# LED_CUBE_V4.net
KiCad netlist of a schematic drawn in EAGLE
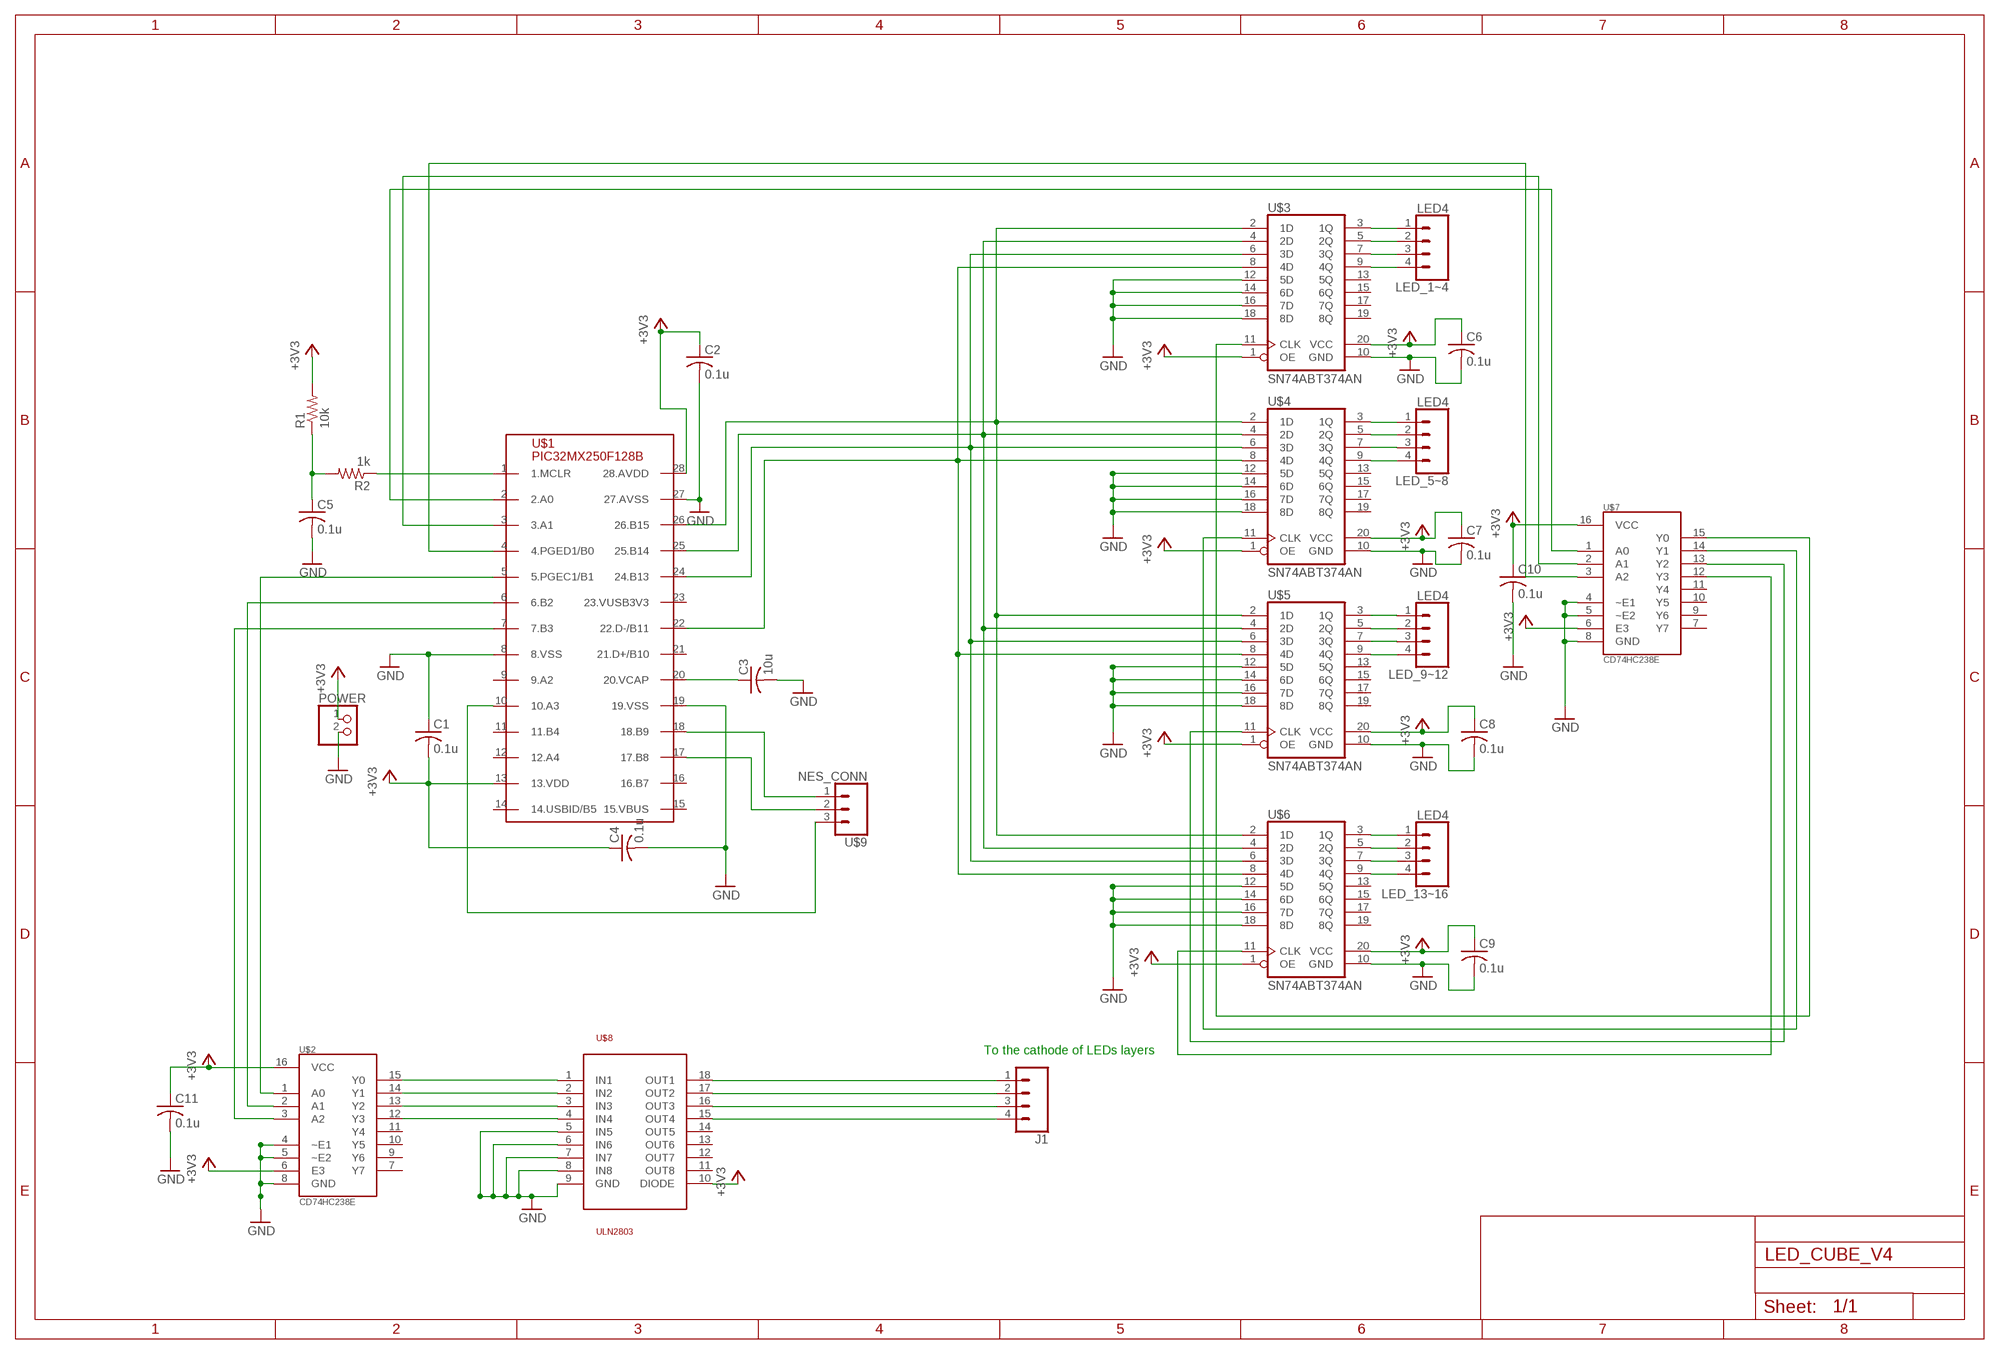
[diagram p0: schematic, sheet 1]

(export (version "E")
  (design (tool "Eeschema 10.0.6"))
  (components
    (comp (ref "C1")
      (value "0.1u")
      (footprint "eagle-import:C025-025X050")
      (libsource (lib "eagle-import") (part "C-US025-025X050"))
    )
    (comp (ref "C2")
      (value "0.1u")
      (footprint "eagle-import:C025-025X050")
      (libsource (lib "eagle-import") (part "C-US025-025X050"))
    )
    (comp (ref "C3")
      (value "10u")
      (footprint "eagle-import:C025-025X050")
      (libsource (lib "eagle-import") (part "C-US025-025X050"))
    )
    (comp (ref "C4")
      (value "0.1u")
      (footprint "eagle-import:C025-025X050")
      (libsource (lib "eagle-import") (part "C-US025-025X050"))
    )
    (comp (ref "C5")
      (value "0.1u")
      (footprint "eagle-import:C025-025X050")
      (libsource (lib "eagle-import") (part "C-US025-025X050"))
    )
    (comp (ref "C6")
      (value "0.1u")
      (footprint "eagle-import:C025-025X050")
      (libsource (lib "eagle-import") (part "C-US025-025X050"))
    )
    (comp (ref "C7")
      (value "0.1u")
      (footprint "eagle-import:C025-025X050")
      (libsource (lib "eagle-import") (part "C-US025-025X050"))
    )
    (comp (ref "C8")
      (value "0.1u")
      (footprint "eagle-import:C025-025X050")
      (libsource (lib "eagle-import") (part "C-US025-025X050"))
    )
    (comp (ref "C9")
      (value "0.1u")
      (footprint "eagle-import:C025-025X050")
      (libsource (lib "eagle-import") (part "C-US025-025X050"))
    )
    (comp (ref "C10")
      (value "0.1u")
      (footprint "eagle-import:C025-025X050")
      (libsource (lib "eagle-import") (part "C-US025-025X050"))
    )
    (comp (ref "C11")
      (value "0.1u")
      (footprint "eagle-import:C025-025X050")
      (libsource (lib "eagle-import") (part "C-US025-025X050"))
    )
    (comp (ref "J1")
      (value "CONN_04")
      (footprint "eagle-import:1X04")
      (libsource (lib "eagle-import") (part "CONN_04"))
    )
    (comp (ref "LED_1~4")
      (value "LED4")
      (footprint "eagle-import:1X04")
      (libsource (lib "eagle-import") (part "LED4"))
    )
    (comp (ref "LED_5~8")
      (value "LED4")
      (footprint "eagle-import:1X04")
      (libsource (lib "eagle-import") (part "LED4"))
    )
    (comp (ref "LED_9~12")
      (value "LED4")
      (footprint "eagle-import:1X04")
      (libsource (lib "eagle-import") (part "LED4"))
    )
    (comp (ref "LED_13~16")
      (value "LED4")
      (footprint "eagle-import:1X04")
      (libsource (lib "eagle-import") (part "LED4"))
    )
    (comp (ref "POWER")
      (value "PINHD-1X2")
      (footprint "eagle-import:1X02")
      (libsource (lib "eagle-import") (part "PINHD-1X2"))
    )
    (comp (ref "R1")
      (value "10k")
      (footprint "eagle-import:0204_7")
      (libsource (lib "eagle-import") (part "R-US_0204/7"))
    )
    (comp (ref "R2")
      (value "1k")
      (footprint "eagle-import:0204_7")
      (libsource (lib "eagle-import") (part "R-US_0204/7"))
    )
    (comp (ref "U$1")
      (value "PIC32MX250F128B")
      (footprint "eagle-import:DIL28-3")
      (libsource (lib "eagle-import") (part "PIC32MX250F128B"))
    )
    (comp (ref "U$2")
      (value "CD74HC238E")
      (footprint "eagle-import:DIL16")
      (libsource (lib "eagle-import") (part "CD74HC238E"))
    )
    (comp (ref "U$3")
      (value "SN74ABT374AN")
      (footprint "eagle-import:DIL20")
      (libsource (lib "eagle-import") (part "SN74ABT374AN"))
    )
    (comp (ref "U$4")
      (value "SN74ABT374AN")
      (footprint "eagle-import:DIL20")
      (libsource (lib "eagle-import") (part "SN74ABT374AN"))
    )
    (comp (ref "U$5")
      (value "SN74ABT374AN")
      (footprint "eagle-import:DIL20")
      (libsource (lib "eagle-import") (part "SN74ABT374AN"))
    )
    (comp (ref "U$6")
      (value "SN74ABT374AN")
      (footprint "eagle-import:DIL20")
      (libsource (lib "eagle-import") (part "SN74ABT374AN"))
    )
    (comp (ref "U$7")
      (value "CD74HC238E")
      (footprint "eagle-import:DIL16")
      (libsource (lib "eagle-import") (part "CD74HC238E"))
    )
    (comp (ref "U$8")
      (value "ULN2803")
      (footprint "eagle-import:SO18L")
      (libsource (lib "eagle-import") (part "ULN2803"))
    )
    (comp (ref "U$9")
      (value "NES_CONN")
      (footprint "eagle-import:1X03")
      (libsource (lib "eagle-import") (part "NES_CONN"))
    )
  )
  (nets
    (net (code "1") (name "+3V3") (class "Default")
      (node (ref "C1") (pin "2") (pinfunction "2_2") (pintype "passive"))
      (node (ref "C10") (pin "1") (pinfunction "1_1") (pintype "passive"))
      (node (ref "C11") (pin "1") (pinfunction "1_1") (pintype "passive"))
      (node (ref "C2") (pin "1") (pinfunction "1_1") (pintype "passive"))
      (node (ref "C4") (pin "1") (pinfunction "1_1") (pintype "passive"))
      (node (ref "C6") (pin "1") (pinfunction "1_1") (pintype "passive"))
      (node (ref "C7") (pin "1") (pinfunction "1_1") (pintype "passive"))
      (node (ref "C8") (pin "1") (pinfunction "1_1") (pintype "passive"))
      (node (ref "C9") (pin "1") (pinfunction "1_1") (pintype "passive"))
      (node (ref "POWER") (pin "1") (pinfunction "1_1") (pintype "passive"))
      (node (ref "R1") (pin "2") (pinfunction "2_2") (pintype "passive"))
      (node (ref "U$1") (pin "13") (pinfunction "13.VDD_13") (pintype "bidirectional"))
      (node (ref "U$1") (pin "28") (pinfunction "28.AVDD_28") (pintype "bidirectional"))
      (node (ref "U$2") (pin "16") (pinfunction "VCC_16") (pintype "bidirectional"))
      (node (ref "U$2") (pin "6") (pinfunction "E3_6") (pintype "bidirectional"))
      (node (ref "U$3") (pin "1") (pinfunction "OE_1") (pintype "input"))
      (node (ref "U$3") (pin "20") (pinfunction "VCC_20") (pintype "bidirectional"))
      (node (ref "U$4") (pin "1") (pinfunction "OE_1") (pintype "input"))
      (node (ref "U$4") (pin "20") (pinfunction "VCC_20") (pintype "bidirectional"))
      (node (ref "U$5") (pin "1") (pinfunction "OE_1") (pintype "input"))
      (node (ref "U$5") (pin "20") (pinfunction "VCC_20") (pintype "bidirectional"))
      (node (ref "U$6") (pin "1") (pinfunction "OE_1") (pintype "input"))
      (node (ref "U$6") (pin "20") (pinfunction "VCC_20") (pintype "bidirectional"))
      (node (ref "U$7") (pin "16") (pinfunction "VCC_16") (pintype "bidirectional"))
      (node (ref "U$7") (pin "6") (pinfunction "E3_6") (pintype "bidirectional"))
      (node (ref "U$8") (pin "10") (pinfunction "DIODE_10") (pintype "power_in"))
    )
    (net (code "2") (name "GND") (class "Default")
      (node (ref "C1") (pin "1") (pinfunction "1_1") (pintype "passive"))
      (node (ref "C10") (pin "2") (pinfunction "2_2") (pintype "passive"))
      (node (ref "C11") (pin "2") (pinfunction "2_2") (pintype "passive"))
      (node (ref "C2") (pin "2") (pinfunction "2_2") (pintype "passive"))
      (node (ref "C3") (pin "2") (pinfunction "2_2") (pintype "passive"))
      (node (ref "C4") (pin "2") (pinfunction "2_2") (pintype "passive"))
      (node (ref "C5") (pin "2") (pinfunction "2_2") (pintype "passive"))
      (node (ref "C6") (pin "2") (pinfunction "2_2") (pintype "passive"))
      (node (ref "C7") (pin "2") (pinfunction "2_2") (pintype "passive"))
      (node (ref "C8") (pin "2") (pinfunction "2_2") (pintype "passive"))
      (node (ref "C9") (pin "2") (pinfunction "2_2") (pintype "passive"))
      (node (ref "POWER") (pin "2") (pinfunction "2_2") (pintype "passive"))
      (node (ref "U$1") (pin "19") (pinfunction "19.VSS_19") (pintype "bidirectional"))
      (node (ref "U$1") (pin "27") (pinfunction "27.AVSS_27") (pintype "bidirectional"))
      (node (ref "U$1") (pin "8") (pinfunction "8.VSS_8") (pintype "bidirectional"))
      (node (ref "U$2") (pin "4") (pinfunction "~{E1}_4") (pintype "bidirectional"))
      (node (ref "U$2") (pin "5") (pinfunction "~{E2}_5") (pintype "bidirectional"))
      (node (ref "U$2") (pin "8") (pinfunction "GND_8") (pintype "bidirectional"))
      (node (ref "U$3") (pin "10") (pinfunction "GND_10") (pintype "bidirectional"))
      (node (ref "U$3") (pin "12") (pinfunction "5D_12") (pintype "input"))
      (node (ref "U$3") (pin "14") (pinfunction "6D_14") (pintype "input"))
      (node (ref "U$3") (pin "16") (pinfunction "7D_16") (pintype "input"))
      (node (ref "U$3") (pin "18") (pinfunction "8D_18") (pintype "input"))
      (node (ref "U$4") (pin "10") (pinfunction "GND_10") (pintype "bidirectional"))
      (node (ref "U$4") (pin "12") (pinfunction "5D_12") (pintype "input"))
      (node (ref "U$4") (pin "14") (pinfunction "6D_14") (pintype "input"))
      (node (ref "U$4") (pin "16") (pinfunction "7D_16") (pintype "input"))
      (node (ref "U$4") (pin "18") (pinfunction "8D_18") (pintype "input"))
      (node (ref "U$5") (pin "10") (pinfunction "GND_10") (pintype "bidirectional"))
      (node (ref "U$5") (pin "12") (pinfunction "5D_12") (pintype "input"))
      (node (ref "U$5") (pin "14") (pinfunction "6D_14") (pintype "input"))
      (node (ref "U$5") (pin "16") (pinfunction "7D_16") (pintype "input"))
      (node (ref "U$5") (pin "18") (pinfunction "8D_18") (pintype "input"))
      (node (ref "U$6") (pin "10") (pinfunction "GND_10") (pintype "bidirectional"))
      (node (ref "U$6") (pin "12") (pinfunction "5D_12") (pintype "input"))
      (node (ref "U$6") (pin "14") (pinfunction "6D_14") (pintype "input"))
      (node (ref "U$6") (pin "16") (pinfunction "7D_16") (pintype "input"))
      (node (ref "U$6") (pin "18") (pinfunction "8D_18") (pintype "input"))
      (node (ref "U$7") (pin "4") (pinfunction "~{E1}_4") (pintype "bidirectional"))
      (node (ref "U$7") (pin "5") (pinfunction "~{E2}_5") (pintype "bidirectional"))
      (node (ref "U$7") (pin "8") (pinfunction "GND_8") (pintype "bidirectional"))
      (node (ref "U$8") (pin "5") (pinfunction "IN5_5") (pintype "input"))
      (node (ref "U$8") (pin "6") (pinfunction "IN6_6") (pintype "input"))
      (node (ref "U$8") (pin "7") (pinfunction "IN7_7") (pintype "input"))
      (node (ref "U$8") (pin "8") (pinfunction "IN8_8") (pintype "input"))
      (node (ref "U$8") (pin "9") (pinfunction "GND_9") (pintype "power_in"))
    )
    (net (code "3") (name "Net-(C5-Pad1)") (class "Default")
      (node (ref "C5") (pin "1") (pinfunction "1_1") (pintype "passive"))
      (node (ref "R1") (pin "1") (pinfunction "1_1") (pintype "passive"))
      (node (ref "R2") (pin "2") (pinfunction "2_2") (pintype "passive"))
    )
    (net (code "4") (name "Net-(U$1-1.MCLR)") (class "Default")
      (node (ref "R2") (pin "1") (pinfunction "1_1") (pintype "passive"))
      (node (ref "U$1") (pin "1") (pinfunction "1.MCLR_1") (pintype "bidirectional"))
    )
    (net (code "5") (name "Net-(U$1-2.A0)") (class "Default")
      (node (ref "U$1") (pin "2") (pinfunction "2.A0_2") (pintype "bidirectional"))
      (node (ref "U$7") (pin "1") (pinfunction "A0_1") (pintype "bidirectional"))
    )
    (net (code "6") (name "Net-(U$1-3.A1)") (class "Default")
      (node (ref "U$1") (pin "3") (pinfunction "3.A1_3") (pintype "bidirectional"))
      (node (ref "U$7") (pin "2") (pinfunction "A1_2") (pintype "bidirectional"))
    )
    (net (code "7") (name "Net-(U$1-4.PGED1{slash}B0)") (class "Default")
      (node (ref "U$1") (pin "4") (pinfunction "4.PGED1/B0_4") (pintype "bidirectional"))
      (node (ref "U$7") (pin "3") (pinfunction "A2_3") (pintype "bidirectional"))
    )
    (net (code "8") (name "Net-(U$1-5.PGEC1{slash}B1)") (class "Default")
      (node (ref "U$1") (pin "5") (pinfunction "5.PGEC1/B1_5") (pintype "bidirectional"))
      (node (ref "U$2") (pin "1") (pinfunction "A0_1") (pintype "bidirectional"))
    )
    (net (code "9") (name "Net-(U$1-6.B2)") (class "Default")
      (node (ref "U$1") (pin "6") (pinfunction "6.B2_6") (pintype "bidirectional"))
      (node (ref "U$2") (pin "2") (pinfunction "A1_2") (pintype "bidirectional"))
    )
    (net (code "10") (name "Net-(U$1-7.B3)") (class "Default")
      (node (ref "U$1") (pin "7") (pinfunction "7.B3_7") (pintype "bidirectional"))
      (node (ref "U$2") (pin "3") (pinfunction "A2_3") (pintype "bidirectional"))
    )
    (net (code "11") (name "Net-(U$1-10.A3)") (class "Default")
      (node (ref "U$1") (pin "10") (pinfunction "10.A3_10") (pintype "bidirectional"))
      (node (ref "U$9") (pin "3") (pinfunction "3_3") (pintype "passive"))
    )
    (net (code "12") (name "Net-(U$1-17.B8)") (class "Default")
      (node (ref "U$1") (pin "17") (pinfunction "17.B8_17") (pintype "bidirectional"))
      (node (ref "U$9") (pin "2") (pinfunction "2_2") (pintype "passive"))
    )
    (net (code "13") (name "Net-(U$1-18.B9)") (class "Default")
      (node (ref "U$1") (pin "18") (pinfunction "18.B9_18") (pintype "bidirectional"))
      (node (ref "U$9") (pin "1") (pinfunction "1_1") (pintype "passive"))
    )
    (net (code "14") (name "Net-(U$1-20.VCAP)") (class "Default")
      (node (ref "C3") (pin "1") (pinfunction "1_1") (pintype "passive"))
      (node (ref "U$1") (pin "20") (pinfunction "20.VCAP_20") (pintype "bidirectional"))
    )
    (net (code "15") (name "Net-(U$1-22.D-{slash}B11)") (class "Default")
      (node (ref "U$1") (pin "22") (pinfunction "22.D-/B11_22") (pintype "bidirectional"))
      (node (ref "U$3") (pin "8") (pinfunction "4D_8") (pintype "input"))
      (node (ref "U$4") (pin "8") (pinfunction "4D_8") (pintype "input"))
      (node (ref "U$5") (pin "8") (pinfunction "4D_8") (pintype "input"))
      (node (ref "U$6") (pin "8") (pinfunction "4D_8") (pintype "input"))
    )
    (net (code "16") (name "Net-(U$1-24.B13)") (class "Default")
      (node (ref "U$1") (pin "24") (pinfunction "24.B13_24") (pintype "bidirectional"))
      (node (ref "U$3") (pin "6") (pinfunction "3D_6") (pintype "input"))
      (node (ref "U$4") (pin "6") (pinfunction "3D_6") (pintype "input"))
      (node (ref "U$5") (pin "6") (pinfunction "3D_6") (pintype "input"))
      (node (ref "U$6") (pin "6") (pinfunction "3D_6") (pintype "input"))
    )
    (net (code "17") (name "Net-(U$1-25.B14)") (class "Default")
      (node (ref "U$1") (pin "25") (pinfunction "25.B14_25") (pintype "bidirectional"))
      (node (ref "U$3") (pin "4") (pinfunction "2D_4") (pintype "input"))
      (node (ref "U$4") (pin "4") (pinfunction "2D_4") (pintype "input"))
      (node (ref "U$5") (pin "4") (pinfunction "2D_4") (pintype "input"))
      (node (ref "U$6") (pin "4") (pinfunction "2D_4") (pintype "input"))
    )
    (net (code "18") (name "Net-(U$1-26.B15)") (class "Default")
      (node (ref "U$1") (pin "26") (pinfunction "26.B15_26") (pintype "bidirectional"))
      (node (ref "U$3") (pin "2") (pinfunction "1D_2") (pintype "input"))
      (node (ref "U$4") (pin "2") (pinfunction "1D_2") (pintype "input"))
      (node (ref "U$5") (pin "2") (pinfunction "1D_2") (pintype "input"))
      (node (ref "U$6") (pin "2") (pinfunction "1D_2") (pintype "input"))
    )
    (net (code "19") (name "Net-(U$2-Y0)") (class "Default")
      (node (ref "U$2") (pin "15") (pinfunction "Y0_15") (pintype "bidirectional"))
      (node (ref "U$8") (pin "1") (pinfunction "IN1_1") (pintype "input"))
    )
    (net (code "20") (name "Net-(U$2-Y1)") (class "Default")
      (node (ref "U$2") (pin "14") (pinfunction "Y1_14") (pintype "bidirectional"))
      (node (ref "U$8") (pin "2") (pinfunction "IN2_2") (pintype "input"))
    )
    (net (code "21") (name "Net-(U$2-Y2)") (class "Default")
      (node (ref "U$2") (pin "13") (pinfunction "Y2_13") (pintype "bidirectional"))
      (node (ref "U$8") (pin "3") (pinfunction "IN3_3") (pintype "input"))
    )
    (net (code "22") (name "Net-(U$2-Y3)") (class "Default")
      (node (ref "U$2") (pin "12") (pinfunction "Y3_12") (pintype "bidirectional"))
      (node (ref "U$8") (pin "4") (pinfunction "IN4_4") (pintype "input"))
    )
    (net (code "23") (name "Net-(U$3-1Q)") (class "Default")
      (node (ref "LED_1~4") (pin "1") (pinfunction "1_1") (pintype "passive"))
      (node (ref "U$3") (pin "3") (pinfunction "1Q_3") (pintype "tri_state"))
    )
    (net (code "24") (name "Net-(U$3-2Q)") (class "Default")
      (node (ref "LED_1~4") (pin "2") (pinfunction "2_2") (pintype "passive"))
      (node (ref "U$3") (pin "5") (pinfunction "2Q_5") (pintype "tri_state"))
    )
    (net (code "25") (name "Net-(U$3-3Q)") (class "Default")
      (node (ref "LED_1~4") (pin "3") (pinfunction "3_3") (pintype "passive"))
      (node (ref "U$3") (pin "7") (pinfunction "3Q_7") (pintype "tri_state"))
    )
    (net (code "26") (name "Net-(U$3-4Q)") (class "Default")
      (node (ref "LED_1~4") (pin "4") (pinfunction "4_4") (pintype "passive"))
      (node (ref "U$3") (pin "9") (pinfunction "4Q_9") (pintype "tri_state"))
    )
    (net (code "27") (name "Net-(U$3-CLK)") (class "Default")
      (node (ref "U$3") (pin "11") (pinfunction "CLK_11") (pintype "input"))
      (node (ref "U$7") (pin "15") (pinfunction "Y0_15") (pintype "bidirectional"))
    )
    (net (code "28") (name "Net-(U$4-1Q)") (class "Default")
      (node (ref "LED_5~8") (pin "1") (pinfunction "1_1") (pintype "passive"))
      (node (ref "U$4") (pin "3") (pinfunction "1Q_3") (pintype "tri_state"))
    )
    (net (code "29") (name "Net-(U$4-2Q)") (class "Default")
      (node (ref "LED_5~8") (pin "2") (pinfunction "2_2") (pintype "passive"))
      (node (ref "U$4") (pin "5") (pinfunction "2Q_5") (pintype "tri_state"))
    )
    (net (code "30") (name "Net-(U$4-3Q)") (class "Default")
      (node (ref "LED_5~8") (pin "3") (pinfunction "3_3") (pintype "passive"))
      (node (ref "U$4") (pin "7") (pinfunction "3Q_7") (pintype "tri_state"))
    )
    (net (code "31") (name "Net-(U$4-4Q)") (class "Default")
      (node (ref "LED_5~8") (pin "4") (pinfunction "4_4") (pintype "passive"))
      (node (ref "U$4") (pin "9") (pinfunction "4Q_9") (pintype "tri_state"))
    )
    (net (code "32") (name "Net-(U$4-CLK)") (class "Default")
      (node (ref "U$4") (pin "11") (pinfunction "CLK_11") (pintype "input"))
      (node (ref "U$7") (pin "14") (pinfunction "Y1_14") (pintype "bidirectional"))
    )
    (net (code "33") (name "Net-(U$5-1Q)") (class "Default")
      (node (ref "LED_9~12") (pin "1") (pinfunction "1_1") (pintype "passive"))
      (node (ref "U$5") (pin "3") (pinfunction "1Q_3") (pintype "tri_state"))
    )
    (net (code "34") (name "Net-(U$5-2Q)") (class "Default")
      (node (ref "LED_9~12") (pin "2") (pinfunction "2_2") (pintype "passive"))
      (node (ref "U$5") (pin "5") (pinfunction "2Q_5") (pintype "tri_state"))
    )
    (net (code "35") (name "Net-(U$5-3Q)") (class "Default")
      (node (ref "LED_9~12") (pin "3") (pinfunction "3_3") (pintype "passive"))
      (node (ref "U$5") (pin "7") (pinfunction "3Q_7") (pintype "tri_state"))
    )
    (net (code "36") (name "Net-(U$5-4Q)") (class "Default")
      (node (ref "LED_9~12") (pin "4") (pinfunction "4_4") (pintype "passive"))
      (node (ref "U$5") (pin "9") (pinfunction "4Q_9") (pintype "tri_state"))
    )
    (net (code "37") (name "Net-(U$5-CLK)") (class "Default")
      (node (ref "U$5") (pin "11") (pinfunction "CLK_11") (pintype "input"))
      (node (ref "U$7") (pin "13") (pinfunction "Y2_13") (pintype "bidirectional"))
    )
    (net (code "38") (name "Net-(U$6-1Q)") (class "Default")
      (node (ref "LED_13~16") (pin "1") (pinfunction "1_1") (pintype "passive"))
      (node (ref "U$6") (pin "3") (pinfunction "1Q_3") (pintype "tri_state"))
    )
    (net (code "39") (name "Net-(U$6-2Q)") (class "Default")
      (node (ref "LED_13~16") (pin "2") (pinfunction "2_2") (pintype "passive"))
      (node (ref "U$6") (pin "5") (pinfunction "2Q_5") (pintype "tri_state"))
    )
    (net (code "40") (name "Net-(U$6-3Q)") (class "Default")
      (node (ref "LED_13~16") (pin "3") (pinfunction "3_3") (pintype "passive"))
      (node (ref "U$6") (pin "7") (pinfunction "3Q_7") (pintype "tri_state"))
    )
    (net (code "41") (name "Net-(U$6-4Q)") (class "Default")
      (node (ref "LED_13~16") (pin "4") (pinfunction "4_4") (pintype "passive"))
      (node (ref "U$6") (pin "9") (pinfunction "4Q_9") (pintype "tri_state"))
    )
    (net (code "42") (name "Net-(U$6-CLK)") (class "Default")
      (node (ref "U$6") (pin "11") (pinfunction "CLK_11") (pintype "input"))
      (node (ref "U$7") (pin "12") (pinfunction "Y3_12") (pintype "bidirectional"))
    )
    (net (code "43") (name "Net-(U$8-OUT1)") (class "Default")
      (node (ref "J1") (pin "1") (pinfunction "1_1") (pintype "passive"))
      (node (ref "U$8") (pin "18") (pinfunction "OUT1_18") (pintype "open_collector"))
    )
    (net (code "44") (name "Net-(U$8-OUT2)") (class "Default")
      (node (ref "J1") (pin "2") (pinfunction "2_2") (pintype "passive"))
      (node (ref "U$8") (pin "17") (pinfunction "OUT2_17") (pintype "open_collector"))
    )
    (net (code "45") (name "Net-(U$8-OUT3)") (class "Default")
      (node (ref "J1") (pin "3") (pinfunction "3_3") (pintype "passive"))
      (node (ref "U$8") (pin "16") (pinfunction "OUT3_16") (pintype "open_collector"))
    )
    (net (code "46") (name "Net-(U$8-OUT4)") (class "Default")
      (node (ref "J1") (pin "4") (pinfunction "4_4") (pintype "passive"))
      (node (ref "U$8") (pin "15") (pinfunction "OUT4_15") (pintype "open_collector"))
    )
    (net (code "47") (name "unconnected-(U$1-9.A2-Pad9)") (class "Default")
      (node (ref "U$1") (pin "9") (pinfunction "9.A2_9") (pintype "bidirectional"))
    )
    (net (code "48") (name "unconnected-(U$1-11.B4-Pad11)") (class "Default")
      (node (ref "U$1") (pin "11") (pinfunction "11.B4_11") (pintype "bidirectional"))
    )
    (net (code "49") (name "unconnected-(U$1-12.A4-Pad12)") (class "Default")
      (node (ref "U$1") (pin "12") (pinfunction "12.A4_12") (pintype "bidirectional"))
    )
    (net (code "50") (name "unconnected-(U$1-14.USBID{slash}B5-Pad14)") (class "Default")
      (node (ref "U$1") (pin "14") (pinfunction "14.USBID/B5_14") (pintype "bidirectional"))
    )
    (net (code "51") (name "unconnected-(U$1-15.VBUS-Pad15)") (class "Default")
      (node (ref "U$1") (pin "15") (pinfunction "15.VBUS_15") (pintype "bidirectional"))
    )
    (net (code "52") (name "unconnected-(U$1-16.B7-Pad16)") (class "Default")
      (node (ref "U$1") (pin "16") (pinfunction "16.B7_16") (pintype "bidirectional"))
    )
    (net (code "53") (name "unconnected-(U$1-21.D+{slash}B10-Pad21)") (class "Default")
      (node (ref "U$1") (pin "21") (pinfunction "21.D+/B10_21") (pintype "bidirectional"))
    )
    (net (code "54") (name "unconnected-(U$1-23.VUSB3V3-Pad23)") (class "Default")
      (node (ref "U$1") (pin "23") (pinfunction "23.VUSB3V3_23") (pintype "bidirectional"))
    )
    (net (code "55") (name "unconnected-(U$2-Y4-Pad11)") (class "Default")
      (node (ref "U$2") (pin "11") (pinfunction "Y4_11") (pintype "bidirectional"))
    )
    (net (code "56") (name "unconnected-(U$2-Y5-Pad10)") (class "Default")
      (node (ref "U$2") (pin "10") (pinfunction "Y5_10") (pintype "bidirectional"))
    )
    (net (code "57") (name "unconnected-(U$2-Y6-Pad9)") (class "Default")
      (node (ref "U$2") (pin "9") (pinfunction "Y6_9") (pintype "bidirectional"))
    )
    (net (code "58") (name "unconnected-(U$2-Y7-Pad7)") (class "Default")
      (node (ref "U$2") (pin "7") (pinfunction "Y7_7") (pintype "bidirectional"))
    )
    (net (code "59") (name "unconnected-(U$3-5Q-Pad13)") (class "Default")
      (node (ref "U$3") (pin "13") (pinfunction "5Q_13") (pintype "tri_state"))
    )
    (net (code "60") (name "unconnected-(U$3-6Q-Pad15)") (class "Default")
      (node (ref "U$3") (pin "15") (pinfunction "6Q_15") (pintype "tri_state"))
    )
    (net (code "61") (name "unconnected-(U$3-7Q-Pad17)") (class "Default")
      (node (ref "U$3") (pin "17") (pinfunction "7Q_17") (pintype "tri_state"))
    )
    (net (code "62") (name "unconnected-(U$3-8Q-Pad19)") (class "Default")
      (node (ref "U$3") (pin "19") (pinfunction "8Q_19") (pintype "tri_state"))
    )
    (net (code "63") (name "unconnected-(U$4-5Q-Pad13)") (class "Default")
      (node (ref "U$4") (pin "13") (pinfunction "5Q_13") (pintype "tri_state"))
    )
    (net (code "64") (name "unconnected-(U$4-6Q-Pad15)") (class "Default")
      (node (ref "U$4") (pin "15") (pinfunction "6Q_15") (pintype "tri_state"))
    )
    (net (code "65") (name "unconnected-(U$4-7Q-Pad17)") (class "Default")
      (node (ref "U$4") (pin "17") (pinfunction "7Q_17") (pintype "tri_state"))
    )
    (net (code "66") (name "unconnected-(U$4-8Q-Pad19)") (class "Default")
      (node (ref "U$4") (pin "19") (pinfunction "8Q_19") (pintype "tri_state"))
    )
    (net (code "67") (name "unconnected-(U$5-5Q-Pad13)") (class "Default")
      (node (ref "U$5") (pin "13") (pinfunction "5Q_13") (pintype "tri_state"))
    )
    (net (code "68") (name "unconnected-(U$5-6Q-Pad15)") (class "Default")
      (node (ref "U$5") (pin "15") (pinfunction "6Q_15") (pintype "tri_state"))
    )
    (net (code "69") (name "unconnected-(U$5-7Q-Pad17)") (class "Default")
      (node (ref "U$5") (pin "17") (pinfunction "7Q_17") (pintype "tri_state"))
    )
    (net (code "70") (name "unconnected-(U$5-8Q-Pad19)") (class "Default")
      (node (ref "U$5") (pin "19") (pinfunction "8Q_19") (pintype "tri_state"))
    )
    (net (code "71") (name "unconnected-(U$6-5Q-Pad13)") (class "Default")
      (node (ref "U$6") (pin "13") (pinfunction "5Q_13") (pintype "tri_state"))
    )
    (net (code "72") (name "unconnected-(U$6-6Q-Pad15)") (class "Default")
      (node (ref "U$6") (pin "15") (pinfunction "6Q_15") (pintype "tri_state"))
    )
    (net (code "73") (name "unconnected-(U$6-7Q-Pad17)") (class "Default")
      (node (ref "U$6") (pin "17") (pinfunction "7Q_17") (pintype "tri_state"))
    )
    (net (code "74") (name "unconnected-(U$6-8Q-Pad19)") (class "Default")
      (node (ref "U$6") (pin "19") (pinfunction "8Q_19") (pintype "tri_state"))
    )
    (net (code "75") (name "unconnected-(U$7-Y4-Pad11)") (class "Default")
      (node (ref "U$7") (pin "11") (pinfunction "Y4_11") (pintype "bidirectional"))
    )
    (net (code "76") (name "unconnected-(U$7-Y5-Pad10)") (class "Default")
      (node (ref "U$7") (pin "10") (pinfunction "Y5_10") (pintype "bidirectional"))
    )
    (net (code "77") (name "unconnected-(U$7-Y6-Pad9)") (class "Default")
      (node (ref "U$7") (pin "9") (pinfunction "Y6_9") (pintype "bidirectional"))
    )
    (net (code "78") (name "unconnected-(U$7-Y7-Pad7)") (class "Default")
      (node (ref "U$7") (pin "7") (pinfunction "Y7_7") (pintype "bidirectional"))
    )
    (net (code "79") (name "unconnected-(U$8-OUT5-Pad14)") (class "Default")
      (node (ref "U$8") (pin "14") (pinfunction "OUT5_14") (pintype "open_collector"))
    )
    (net (code "80") (name "unconnected-(U$8-OUT6-Pad13)") (class "Default")
      (node (ref "U$8") (pin "13") (pinfunction "OUT6_13") (pintype "open_collector"))
    )
    (net (code "81") (name "unconnected-(U$8-OUT7-Pad12)") (class "Default")
      (node (ref "U$8") (pin "12") (pinfunction "OUT7_12") (pintype "open_collector"))
    )
    (net (code "82") (name "unconnected-(U$8-OUT8-Pad11)") (class "Default")
      (node (ref "U$8") (pin "11") (pinfunction "OUT8_11") (pintype "open_collector"))
    )
  )
)
